# untitled.net
KiCad netlist of a schematic drawn in EAGLE
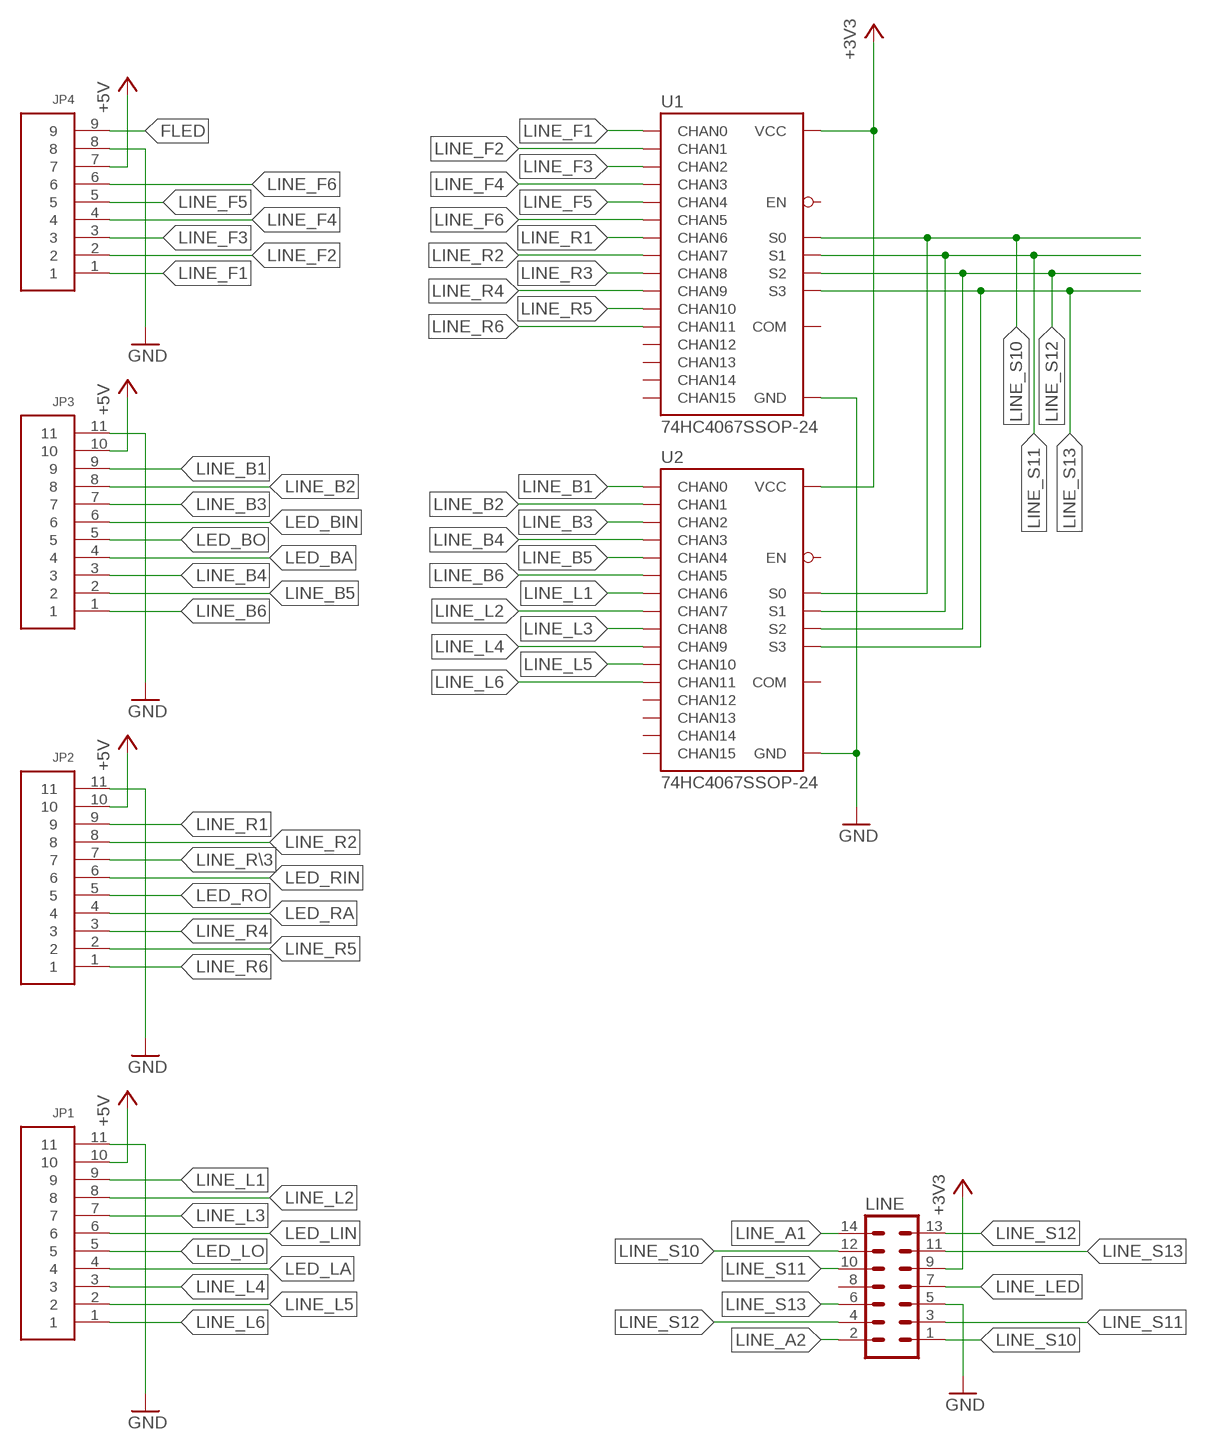
[diagram p0: schematic, sheet 1]

(export (version "E")
  (design (tool "Eeschema 10.0.6"))
  (components
    (comp (ref "JP1")
      (value "11PIN")
      (footprint "eagle-import:B11B-PH-K-S")
      (libsource (lib "eagle-import") (part "11PIN"))
    )
    (comp (ref "JP2")
      (value "11PIN")
      (footprint "eagle-import:B11B-PH-K-S")
      (libsource (lib "eagle-import") (part "11PIN"))
    )
    (comp (ref "JP3")
      (value "11PIN")
      (footprint "eagle-import:B11B-PH-K-S")
      (libsource (lib "eagle-import") (part "11PIN"))
    )
    (comp (ref "JP4")
      (value "9PIN")
      (footprint "eagle-import:B9B-PH-K-S")
      (libsource (lib "eagle-import") (part "9PIN"))
    )
    (comp (ref "LINE")
      (value "MA07-2")
      (footprint "eagle-import:MA07-2")
      (libsource (lib "eagle-import") (part "MA07-2"))
    )
    (comp (ref "U1")
      (value "74HC4067SSOP-24")
      (footprint "eagle-import:SSOP24")
      (fields (field (name "MF") "Nexperia") (field (name "MP") "74HC4067"))
      (libsource (lib "eagle-import") (part "74HC4067SSOP-24"))
    )
    (comp (ref "U2")
      (value "74HC4067SSOP-24")
      (footprint "eagle-import:SSOP24")
      (fields (field (name "MF") "Nexperia") (field (name "MP") "74HC4067"))
      (libsource (lib "eagle-import") (part "74HC4067SSOP-24"))
    )
  )
  (nets
    (net (code "1") (name "+3V3") (class "Default")
      (node (ref "LINE") (pin "9") (pinfunction "9_9") (pintype "passive"))
      (node (ref "U1") (pin "24") (pinfunction "VCC_24") (pintype "bidirectional"))
      (node (ref "U2") (pin "24") (pinfunction "VCC_24") (pintype "bidirectional"))
    )
    (net (code "2") (name "+5V") (class "Default")
      (node (ref "JP1") (pin "10") (pinfunction "10_10") (pintype "bidirectional"))
      (node (ref "JP2") (pin "10") (pinfunction "10_10") (pintype "bidirectional"))
      (node (ref "JP3") (pin "10") (pinfunction "10_10") (pintype "bidirectional"))
      (node (ref "JP4") (pin "7") (pinfunction "7_7") (pintype "bidirectional"))
    )
    (net (code "3") (name "FLED") (class "Default")
      (node (ref "JP4") (pin "9") (pinfunction "9_9") (pintype "bidirectional"))
    )
    (net (code "4") (name "GND") (class "Default")
      (node (ref "JP1") (pin "11") (pinfunction "11_11") (pintype "bidirectional"))
      (node (ref "JP2") (pin "11") (pinfunction "11_11") (pintype "bidirectional"))
      (node (ref "JP3") (pin "11") (pinfunction "11_11") (pintype "bidirectional"))
      (node (ref "JP4") (pin "8") (pinfunction "8_8") (pintype "bidirectional"))
      (node (ref "LINE") (pin "5") (pinfunction "5_5") (pintype "passive"))
      (node (ref "U1") (pin "12") (pinfunction "GND_12") (pintype "bidirectional"))
      (node (ref "U2") (pin "12") (pinfunction "GND_12") (pintype "bidirectional"))
    )
    (net (code "5") (name "LED_BA") (class "Default")
      (node (ref "JP3") (pin "4") (pinfunction "4_4") (pintype "bidirectional"))
    )
    (net (code "6") (name "LED_BIN") (class "Default")
      (node (ref "JP3") (pin "6") (pinfunction "6_6") (pintype "bidirectional"))
    )
    (net (code "7") (name "LED_BO") (class "Default")
      (node (ref "JP3") (pin "5") (pinfunction "5_5") (pintype "bidirectional"))
    )
    (net (code "8") (name "LED_LA") (class "Default")
      (node (ref "JP1") (pin "4") (pinfunction "4_4") (pintype "bidirectional"))
    )
    (net (code "9") (name "LED_LIN") (class "Default")
      (node (ref "JP1") (pin "6") (pinfunction "6_6") (pintype "bidirectional"))
    )
    (net (code "10") (name "LED_LO") (class "Default")
      (node (ref "JP1") (pin "5") (pinfunction "5_5") (pintype "bidirectional"))
    )
    (net (code "11") (name "LED_RA") (class "Default")
      (node (ref "JP2") (pin "4") (pinfunction "4_4") (pintype "bidirectional"))
    )
    (net (code "12") (name "LED_RIN") (class "Default")
      (node (ref "JP2") (pin "6") (pinfunction "6_6") (pintype "bidirectional"))
    )
    (net (code "13") (name "LED_RO") (class "Default")
      (node (ref "JP2") (pin "5") (pinfunction "5_5") (pintype "bidirectional"))
    )
    (net (code "14") (name "LINE_A1") (class "Default")
      (node (ref "LINE") (pin "14") (pinfunction "14_14") (pintype "passive"))
    )
    (net (code "15") (name "LINE_A2") (class "Default")
      (node (ref "LINE") (pin "2") (pinfunction "2_2") (pintype "passive"))
    )
    (net (code "16") (name "LINE_B1") (class "Default")
      (node (ref "JP3") (pin "9") (pinfunction "9_9") (pintype "bidirectional"))
      (node (ref "U2") (pin "9") (pinfunction "CHAN0_9") (pintype "bidirectional"))
    )
    (net (code "17") (name "LINE_B2") (class "Default")
      (node (ref "JP3") (pin "8") (pinfunction "8_8") (pintype "bidirectional"))
      (node (ref "U2") (pin "8") (pinfunction "CHAN1_8") (pintype "bidirectional"))
    )
    (net (code "18") (name "LINE_B3") (class "Default")
      (node (ref "JP3") (pin "7") (pinfunction "7_7") (pintype "bidirectional"))
      (node (ref "U2") (pin "7") (pinfunction "CHAN2_7") (pintype "bidirectional"))
    )
    (net (code "19") (name "LINE_B4") (class "Default")
      (node (ref "JP3") (pin "3") (pinfunction "3_3") (pintype "bidirectional"))
      (node (ref "U2") (pin "6") (pinfunction "CHAN3_6") (pintype "bidirectional"))
    )
    (net (code "20") (name "LINE_B5") (class "Default")
      (node (ref "JP3") (pin "2") (pinfunction "2_2") (pintype "bidirectional"))
      (node (ref "U2") (pin "5") (pinfunction "CHAN4_5") (pintype "bidirectional"))
    )
    (net (code "21") (name "LINE_B6") (class "Default")
      (node (ref "JP3") (pin "1") (pinfunction "1_1") (pintype "bidirectional"))
      (node (ref "U2") (pin "4") (pinfunction "CHAN5_4") (pintype "bidirectional"))
    )
    (net (code "22") (name "LINE_F1") (class "Default")
      (node (ref "JP4") (pin "1") (pinfunction "1_1") (pintype "bidirectional"))
      (node (ref "U1") (pin "9") (pinfunction "CHAN0_9") (pintype "bidirectional"))
    )
    (net (code "23") (name "LINE_F2") (class "Default")
      (node (ref "JP4") (pin "2") (pinfunction "2_2") (pintype "bidirectional"))
      (node (ref "U1") (pin "8") (pinfunction "CHAN1_8") (pintype "bidirectional"))
    )
    (net (code "24") (name "LINE_F3") (class "Default")
      (node (ref "JP4") (pin "3") (pinfunction "3_3") (pintype "bidirectional"))
      (node (ref "U1") (pin "7") (pinfunction "CHAN2_7") (pintype "bidirectional"))
    )
    (net (code "25") (name "LINE_F4") (class "Default")
      (node (ref "JP4") (pin "4") (pinfunction "4_4") (pintype "bidirectional"))
      (node (ref "U1") (pin "6") (pinfunction "CHAN3_6") (pintype "bidirectional"))
    )
    (net (code "26") (name "LINE_F5") (class "Default")
      (node (ref "JP4") (pin "5") (pinfunction "5_5") (pintype "bidirectional"))
      (node (ref "U1") (pin "5") (pinfunction "CHAN4_5") (pintype "bidirectional"))
    )
    (net (code "27") (name "LINE_F6") (class "Default")
      (node (ref "JP4") (pin "6") (pinfunction "6_6") (pintype "bidirectional"))
      (node (ref "U1") (pin "4") (pinfunction "CHAN5_4") (pintype "bidirectional"))
    )
    (net (code "28") (name "LINE_L1") (class "Default")
      (node (ref "JP1") (pin "9") (pinfunction "9_9") (pintype "bidirectional"))
      (node (ref "U2") (pin "3") (pinfunction "CHAN6_3") (pintype "bidirectional"))
    )
    (net (code "29") (name "LINE_L2") (class "Default")
      (node (ref "JP1") (pin "8") (pinfunction "8_8") (pintype "bidirectional"))
      (node (ref "U2") (pin "2") (pinfunction "CHAN7_2") (pintype "bidirectional"))
    )
    (net (code "30") (name "LINE_L3") (class "Default")
      (node (ref "JP1") (pin "7") (pinfunction "7_7") (pintype "bidirectional"))
      (node (ref "U2") (pin "23") (pinfunction "CHAN8_23") (pintype "bidirectional"))
    )
    (net (code "31") (name "LINE_L4") (class "Default")
      (node (ref "JP1") (pin "3") (pinfunction "3_3") (pintype "bidirectional"))
      (node (ref "U2") (pin "22") (pinfunction "CHAN9_22") (pintype "bidirectional"))
    )
    (net (code "32") (name "LINE_L5") (class "Default")
      (node (ref "JP1") (pin "2") (pinfunction "2_2") (pintype "bidirectional"))
      (node (ref "U2") (pin "21") (pinfunction "CHAN10_21") (pintype "bidirectional"))
    )
    (net (code "33") (name "LINE_L6") (class "Default")
      (node (ref "JP1") (pin "1") (pinfunction "1_1") (pintype "bidirectional"))
      (node (ref "U2") (pin "20") (pinfunction "CHAN11_20") (pintype "bidirectional"))
    )
    (net (code "34") (name "LINE_LED") (class "Default")
      (node (ref "LINE") (pin "7") (pinfunction "7_7") (pintype "passive"))
    )
    (net (code "35") (name "LINE_R1") (class "Default")
      (node (ref "JP2") (pin "9") (pinfunction "9_9") (pintype "bidirectional"))
      (node (ref "U1") (pin "3") (pinfunction "CHAN6_3") (pintype "bidirectional"))
    )
    (net (code "36") (name "LINE_R2") (class "Default")
      (node (ref "JP2") (pin "8") (pinfunction "8_8") (pintype "bidirectional"))
      (node (ref "U1") (pin "2") (pinfunction "CHAN7_2") (pintype "bidirectional"))
    )
    (net (code "37") (name "LINE_R3") (class "Default")
      (node (ref "U1") (pin "23") (pinfunction "CHAN8_23") (pintype "bidirectional"))
    )
    (net (code "38") (name "LINE_R4") (class "Default")
      (node (ref "JP2") (pin "3") (pinfunction "3_3") (pintype "bidirectional"))
      (node (ref "U1") (pin "22") (pinfunction "CHAN9_22") (pintype "bidirectional"))
    )
    (net (code "39") (name "LINE_R5") (class "Default")
      (node (ref "JP2") (pin "2") (pinfunction "2_2") (pintype "bidirectional"))
      (node (ref "U1") (pin "21") (pinfunction "CHAN10_21") (pintype "bidirectional"))
    )
    (net (code "40") (name "LINE_R6") (class "Default")
      (node (ref "JP2") (pin "1") (pinfunction "1_1") (pintype "bidirectional"))
      (node (ref "U1") (pin "20") (pinfunction "CHAN11_20") (pintype "bidirectional"))
    )
    (net (code "41") (name "LINE_R\\3") (class "Default")
      (node (ref "JP2") (pin "7") (pinfunction "7_7") (pintype "bidirectional"))
    )
    (net (code "42") (name "LINE_S10") (class "Default")
      (node (ref "LINE") (pin "1") (pinfunction "1_1") (pintype "passive"))
      (node (ref "LINE") (pin "12") (pinfunction "12_12") (pintype "passive"))
      (node (ref "U1") (pin "10") (pinfunction "S0_10") (pintype "input"))
      (node (ref "U2") (pin "10") (pinfunction "S0_10") (pintype "input"))
    )
    (net (code "43") (name "LINE_S11") (class "Default")
      (node (ref "LINE") (pin "10") (pinfunction "10_10") (pintype "passive"))
      (node (ref "LINE") (pin "3") (pinfunction "3_3") (pintype "passive"))
      (node (ref "U1") (pin "11") (pinfunction "S1_11") (pintype "input"))
      (node (ref "U2") (pin "11") (pinfunction "S1_11") (pintype "input"))
    )
    (net (code "44") (name "LINE_S12") (class "Default")
      (node (ref "LINE") (pin "13") (pinfunction "13_13") (pintype "passive"))
      (node (ref "LINE") (pin "4") (pinfunction "4_4") (pintype "passive"))
      (node (ref "U1") (pin "14") (pinfunction "S2_14") (pintype "input"))
      (node (ref "U2") (pin "14") (pinfunction "S2_14") (pintype "input"))
    )
    (net (code "45") (name "LINE_S13") (class "Default")
      (node (ref "LINE") (pin "11") (pinfunction "11_11") (pintype "passive"))
      (node (ref "LINE") (pin "6") (pinfunction "6_6") (pintype "passive"))
      (node (ref "U1") (pin "13") (pinfunction "S3_13") (pintype "input"))
      (node (ref "U2") (pin "13") (pinfunction "S3_13") (pintype "input"))
    )
    (net (code "46") (name "unconnected-(LINE-Pad8)") (class "Default")
      (node (ref "LINE") (pin "8") (pinfunction "8_8") (pintype "passive"))
    )
    (net (code "47") (name "unconnected-(U1-CHAN12-Pad19)") (class "Default")
      (node (ref "U1") (pin "19") (pinfunction "CHAN12_19") (pintype "bidirectional"))
    )
    (net (code "48") (name "unconnected-(U1-CHAN13-Pad18)") (class "Default")
      (node (ref "U1") (pin "18") (pinfunction "CHAN13_18") (pintype "bidirectional"))
    )
    (net (code "49") (name "unconnected-(U1-CHAN14-Pad17)") (class "Default")
      (node (ref "U1") (pin "17") (pinfunction "CHAN14_17") (pintype "bidirectional"))
    )
    (net (code "50") (name "unconnected-(U1-CHAN15-Pad16)") (class "Default")
      (node (ref "U1") (pin "16") (pinfunction "CHAN15_16") (pintype "bidirectional"))
    )
    (net (code "51") (name "unconnected-(U1-COM-Pad1)") (class "Default")
      (node (ref "U1") (pin "1") (pinfunction "COM_1") (pintype "bidirectional"))
    )
    (net (code "52") (name "unconnected-(U1-EN-Pad15)") (class "Default")
      (node (ref "U1") (pin "15") (pinfunction "EN_15") (pintype "input"))
    )
    (net (code "53") (name "unconnected-(U2-CHAN12-Pad19)") (class "Default")
      (node (ref "U2") (pin "19") (pinfunction "CHAN12_19") (pintype "bidirectional"))
    )
    (net (code "54") (name "unconnected-(U2-CHAN13-Pad18)") (class "Default")
      (node (ref "U2") (pin "18") (pinfunction "CHAN13_18") (pintype "bidirectional"))
    )
    (net (code "55") (name "unconnected-(U2-CHAN14-Pad17)") (class "Default")
      (node (ref "U2") (pin "17") (pinfunction "CHAN14_17") (pintype "bidirectional"))
    )
    (net (code "56") (name "unconnected-(U2-CHAN15-Pad16)") (class "Default")
      (node (ref "U2") (pin "16") (pinfunction "CHAN15_16") (pintype "bidirectional"))
    )
    (net (code "57") (name "unconnected-(U2-COM-Pad1)") (class "Default")
      (node (ref "U2") (pin "1") (pinfunction "COM_1") (pintype "bidirectional"))
    )
    (net (code "58") (name "unconnected-(U2-EN-Pad15)") (class "Default")
      (node (ref "U2") (pin "15") (pinfunction "EN_15") (pintype "input"))
    )
  )
)
